# sx3_io_tach.net
KiCad netlist of a schematic drawn in EAGLE
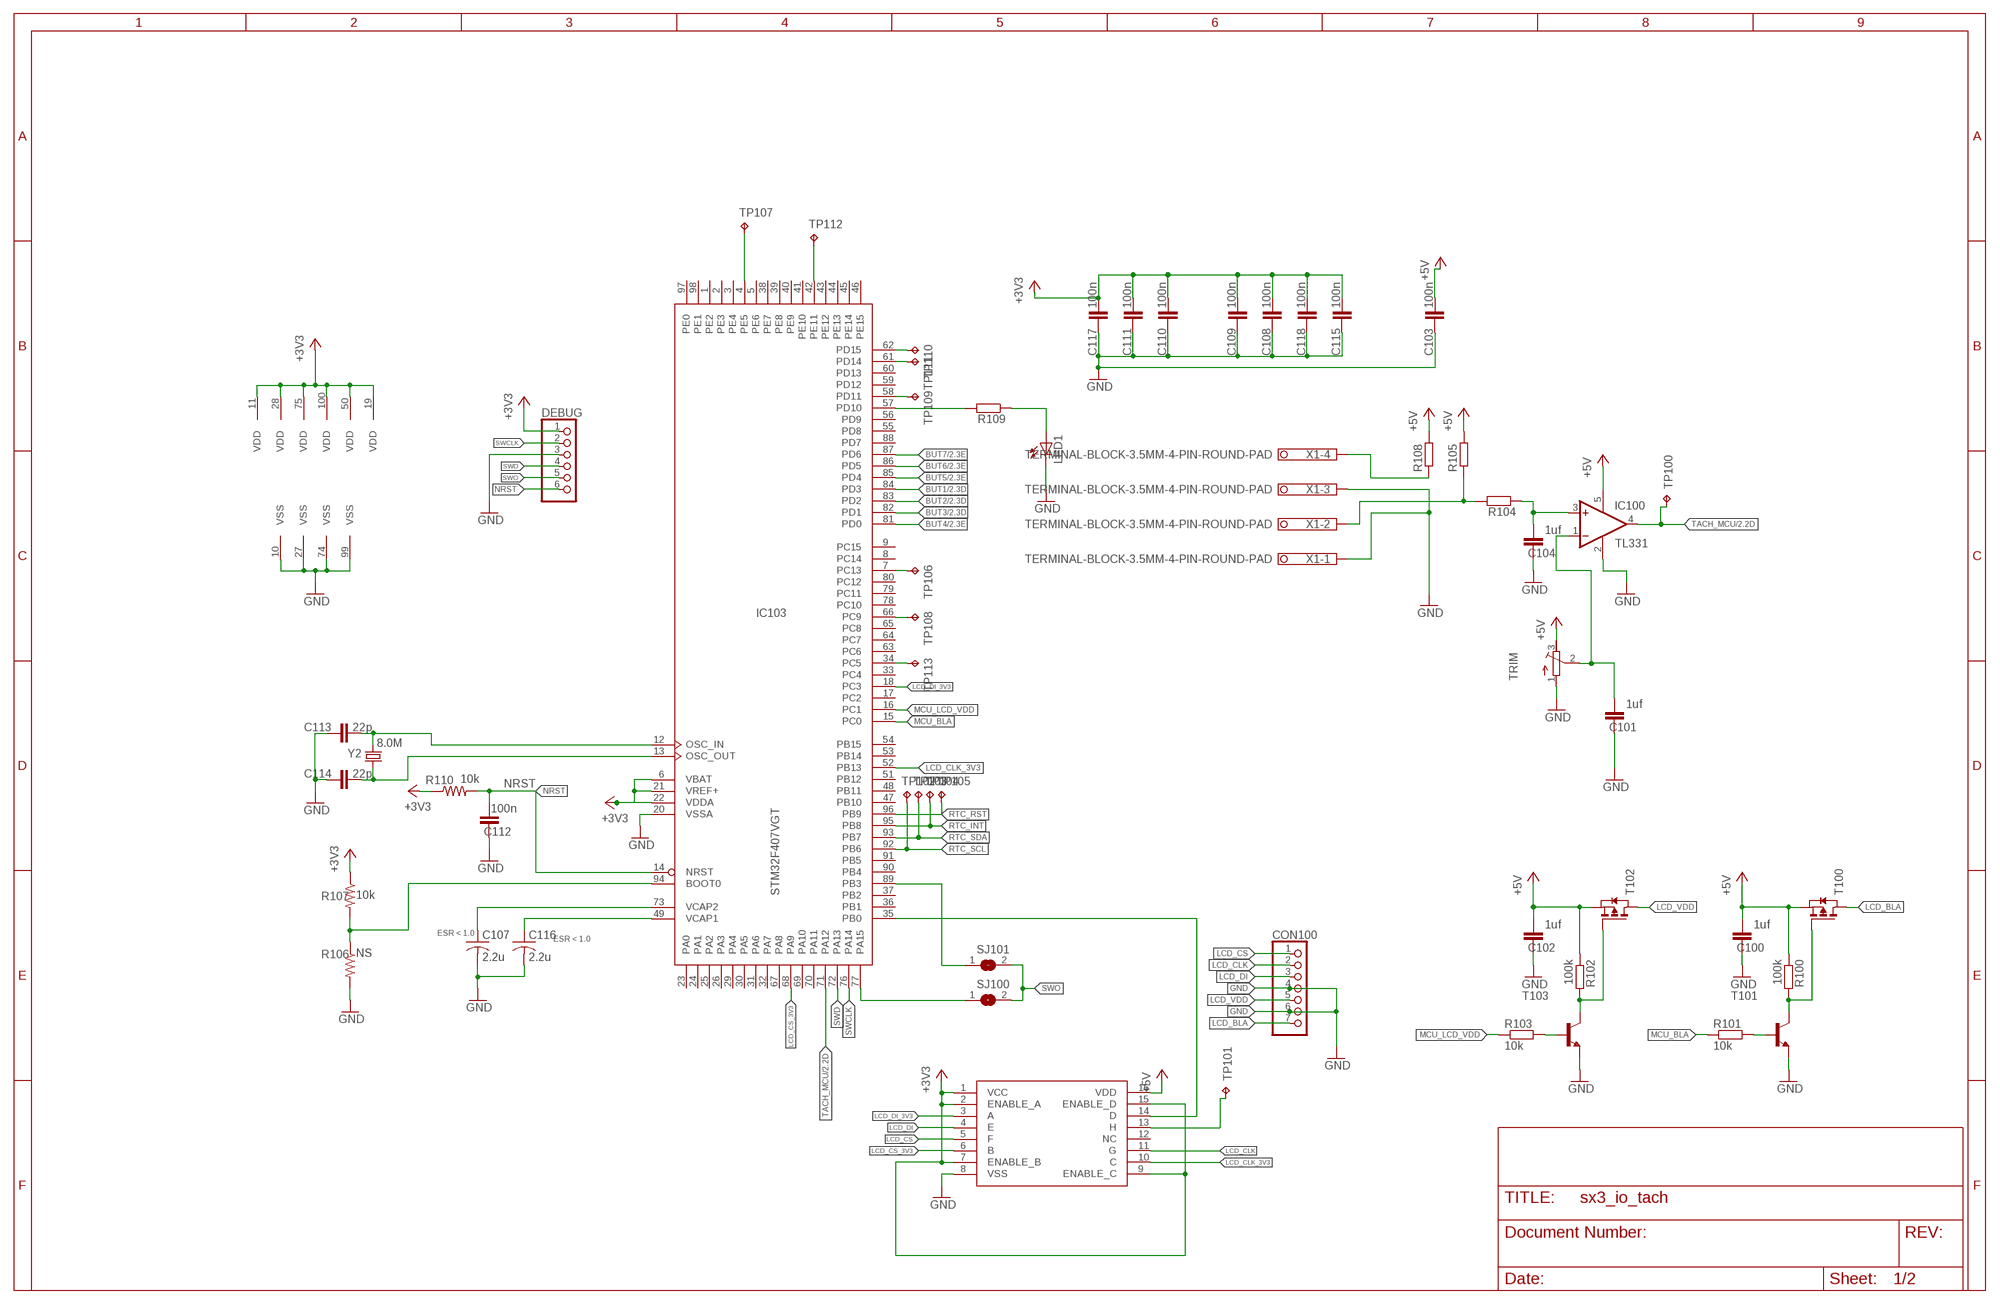
[diagram p0: schematic, sheet 1]
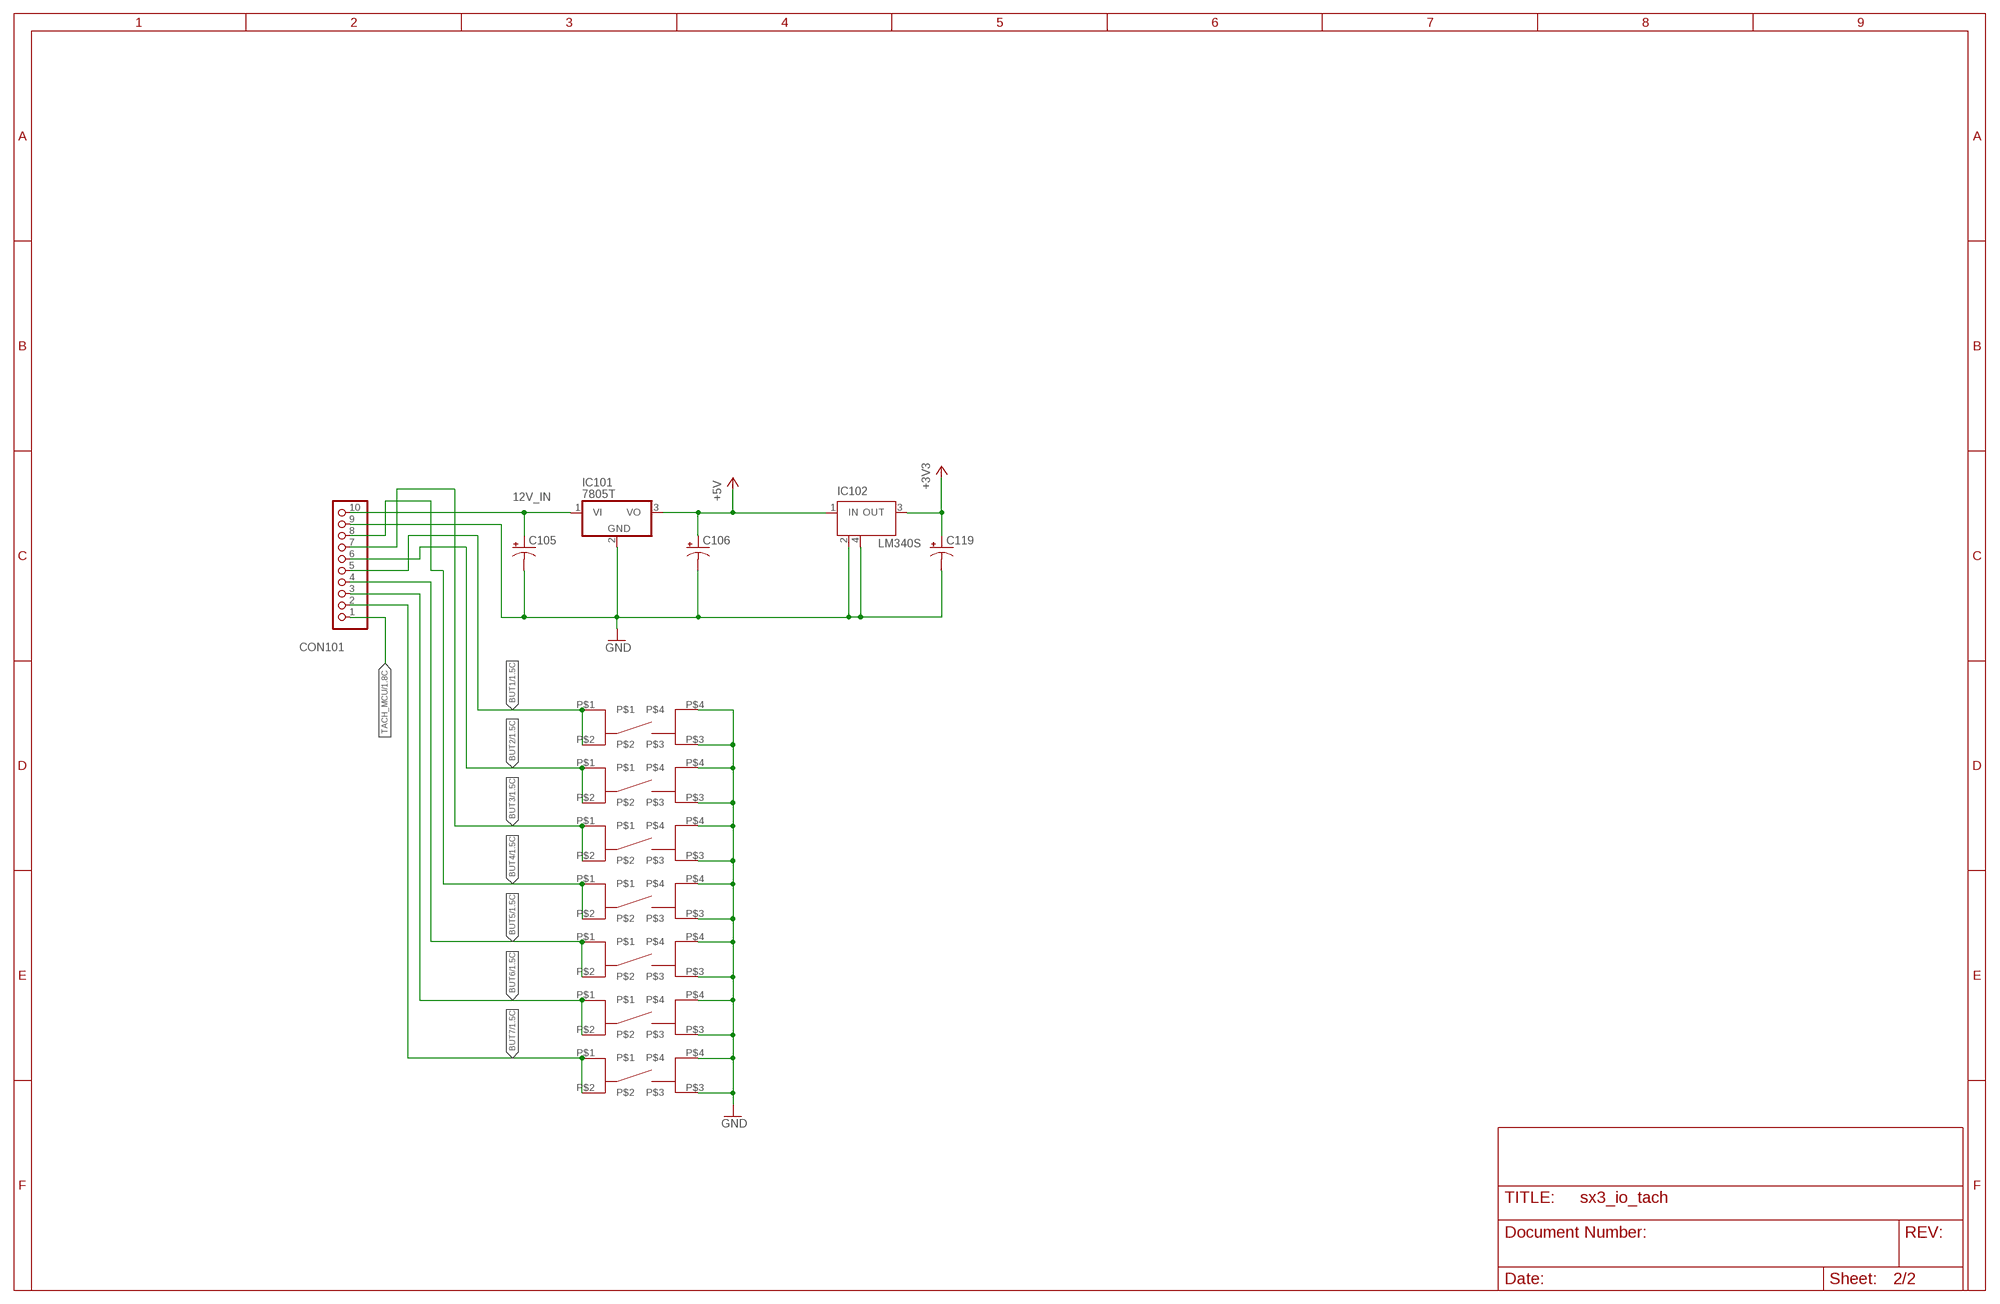
[diagram p1: schematic, sheet 2]

(export (version "E")
  (design (tool "Eeschema 10.0.6"))
  (components
    (comp (ref "C105")
      (value "CPOL-USE2,5-6E")
      (footprint "eagle-import:E2,5-6E")
      (libsource (lib "eagle-import") (part "CPOL-USE2,5-6E"))
    )
    (comp (ref "C106")
      (value "CPOL-USE2,5-6E")
      (footprint "eagle-import:E2,5-6E")
      (libsource (lib "eagle-import") (part "CPOL-USE2,5-6E"))
    )
    (comp (ref "C119")
      (value "CPOL-USE2,5-6E")
      (footprint "eagle-import:E2,5-6E")
      (libsource (lib "eagle-import") (part "CPOL-USE2,5-6E"))
    )
    (comp (ref "CON101")
      (value "PINHD-1X10")
      (footprint "eagle-import:1X10")
      (libsource (lib "eagle-import") (part "PINHD-1X10"))
    )
    (comp (ref "IC101")
      (value "7805T")
      (footprint "eagle-import:TO220H")
      (libsource (lib "eagle-import") (part "78T05"))
    )
    (comp (ref "IC102")
      (value "LM340S")
      (footprint "eagle-import:SOT223")
      (libsource (lib "eagle-import") (part "LM340S"))
    )
    (comp (ref "U$1")
      (value "TE_2-1825910")
      (footprint "eagle-import:TE_2-1825910-7")
      (libsource (lib "eagle-import") (part "TE_2-1825910"))
    )
    (comp (ref "U$2")
      (value "TE_2-1825910")
      (footprint "eagle-import:TE_2-1825910-7")
      (libsource (lib "eagle-import") (part "TE_2-1825910"))
    )
    (comp (ref "U$3")
      (value "TE_2-1825910")
      (footprint "eagle-import:TE_2-1825910-7")
      (libsource (lib "eagle-import") (part "TE_2-1825910"))
    )
    (comp (ref "U$4")
      (value "TE_2-1825910")
      (footprint "eagle-import:TE_2-1825910-7")
      (libsource (lib "eagle-import") (part "TE_2-1825910"))
    )
    (comp (ref "U$5")
      (value "TE_2-1825910")
      (footprint "eagle-import:TE_2-1825910-7")
      (libsource (lib "eagle-import") (part "TE_2-1825910"))
    )
    (comp (ref "U$6")
      (value "TE_2-1825910")
      (footprint "eagle-import:TE_2-1825910-7")
      (libsource (lib "eagle-import") (part "TE_2-1825910"))
    )
    (comp (ref "U$7")
      (value "TE_2-1825910")
      (footprint "eagle-import:TE_2-1825910-7")
      (libsource (lib "eagle-import") (part "TE_2-1825910"))
    )
    (comp (ref "C100")
      (value "1uf")
      (footprint "eagle-import:C0603K")
      (libsource (lib "eagle-import") (part "C-EUC0603K"))
    )
    (comp (ref "C101")
      (value "1uf")
      (footprint "eagle-import:C0603K")
      (libsource (lib "eagle-import") (part "C-EUC0603K"))
    )
    (comp (ref "C102")
      (value "1uf")
      (footprint "eagle-import:C0603K")
      (libsource (lib "eagle-import") (part "C-EUC0603K"))
    )
    (comp (ref "C103")
      (value "100n")
      (footprint "eagle-import:C0603K")
      (libsource (lib "eagle-import") (part "C-EUC0603K"))
    )
    (comp (ref "C104")
      (value "1uf")
      (footprint "eagle-import:C0603K")
      (libsource (lib "eagle-import") (part "C-EUC0603K"))
    )
    (comp (ref "C107")
      (value "2.2u")
      (footprint "eagle-import:C1206")
      (libsource (lib "eagle-import") (part "C-USC1206"))
    )
    (comp (ref "C108")
      (value "100n")
      (footprint "eagle-import:C0603K")
      (libsource (lib "eagle-import") (part "C-EUC0603K"))
    )
    (comp (ref "C109")
      (value "100n")
      (footprint "eagle-import:C0603K")
      (libsource (lib "eagle-import") (part "C-EUC0603K"))
    )
    (comp (ref "C110")
      (value "100n")
      (footprint "eagle-import:C0603K")
      (libsource (lib "eagle-import") (part "C-EUC0603K"))
    )
    (comp (ref "C111")
      (value "100n")
      (footprint "eagle-import:C0603K")
      (libsource (lib "eagle-import") (part "C-EUC0603K"))
    )
    (comp (ref "C112")
      (value "100n")
      (footprint "eagle-import:C0603K")
      (libsource (lib "eagle-import") (part "C-EUC0603K"))
    )
    (comp (ref "C113")
      (value "22p")
      (footprint "eagle-import:C0603K")
      (libsource (lib "eagle-import") (part "C-EUC0603K"))
    )
    (comp (ref "C114")
      (value "22p")
      (footprint "eagle-import:C0603K")
      (libsource (lib "eagle-import") (part "C-EUC0603K"))
    )
    (comp (ref "C115")
      (value "100n")
      (footprint "eagle-import:C0603K")
      (libsource (lib "eagle-import") (part "C-EUC0603K"))
    )
    (comp (ref "C116")
      (value "2.2u")
      (footprint "eagle-import:C1206")
      (libsource (lib "eagle-import") (part "C-USC1206"))
    )
    (comp (ref "C117")
      (value "100n")
      (footprint "eagle-import:C0603K")
      (libsource (lib "eagle-import") (part "C-EUC0603K"))
    )
    (comp (ref "C118")
      (value "100n")
      (footprint "eagle-import:C0603K")
      (libsource (lib "eagle-import") (part "C-EUC0603K"))
    )
    (comp (ref "CON100")
      (value "PINHD-1X7")
      (footprint "eagle-import:1X07")
      (libsource (lib "eagle-import") (part "PINHD-1X7"))
    )
    (comp (ref "DEBUG")
      (value "PINHD-1X6")
      (footprint "eagle-import:1X06")
      (libsource (lib "eagle-import") (part "PINHD-1X6"))
    )
    (comp (ref "IC100")
      (value "TL331")
      (footprint "eagle-import:DBV-R-PDSO-G5")
      (libsource (lib "eagle-import") (part "TL331"))
    )
    (comp (ref "IC103")
      (value "STM32F407VGT")
      (footprint "eagle-import:LQFP100")
      (libsource (lib "eagle-import") (part "STM32F407VTG"))
    )
    (comp (ref "LED1")
      (value "LED_ELD260")
      (footprint "eagle-import:LED_LD260")
      (libsource (lib "eagle-import") (part "LED_ELD260"))
    )
    (comp (ref "R100")
      (value "100k")
      (footprint "eagle-import:R0603")
      (libsource (lib "eagle-import") (part "R-EU_R0603"))
    )
    (comp (ref "R101")
      (value "10k")
      (footprint "eagle-import:R0603")
      (libsource (lib "eagle-import") (part "R-EU_R0603"))
    )
    (comp (ref "R102")
      (value "100k")
      (footprint "eagle-import:R0603")
      (libsource (lib "eagle-import") (part "R-EU_R0603"))
    )
    (comp (ref "R103")
      (value "10k")
      (footprint "eagle-import:R0603")
      (libsource (lib "eagle-import") (part "R-EU_R0603"))
    )
    (comp (ref "R104")
      (value "R-EU_R0603")
      (footprint "eagle-import:R0603")
      (libsource (lib "eagle-import") (part "R-EU_R0603"))
    )
    (comp (ref "R105")
      (value "R-EU_R0603")
      (footprint "eagle-import:R0603")
      (libsource (lib "eagle-import") (part "R-EU_R0603"))
    )
    (comp (ref "R106")
      (value "NS")
      (footprint "eagle-import:R0603")
      (libsource (lib "eagle-import") (part "R-US_R0603"))
    )
    (comp (ref "R107")
      (value "10k")
      (footprint "eagle-import:R0603")
      (libsource (lib "eagle-import") (part "R-US_R0603"))
    )
    (comp (ref "R108")
      (value "R-EU_R0603")
      (footprint "eagle-import:R0603")
      (libsource (lib "eagle-import") (part "R-EU_R0603"))
    )
    (comp (ref "R109")
      (value "R-EU_R0603")
      (footprint "eagle-import:R0603")
      (libsource (lib "eagle-import") (part "R-EU_R0603"))
    )
    (comp (ref "R110")
      (value "10k")
      (footprint "eagle-import:R0603")
      (libsource (lib "eagle-import") (part "R-US_R0603"))
    )
    (comp (ref "SJ100")
      (value "SJ")
      (footprint "eagle-import:SJ")
      (libsource (lib "eagle-import") (part "SJ"))
    )
    (comp (ref "SJ101")
      (value "SJ")
      (footprint "eagle-import:SJ")
      (libsource (lib "eagle-import") (part "SJ"))
    )
    (comp (ref "T100")
      (value "PMOSSOT23")
      (footprint "eagle-import:SOT-23")
      (libsource (lib "eagle-import") (part "PMOSSOT23"))
    )
    (comp (ref "T101")
      (value "BC817-NPN-SOT23-BEC")
      (footprint "eagle-import:SOT23-BEC")
      (libsource (lib "eagle-import") (part "-NPN-SOT23-BECBC817"))
    )
    (comp (ref "T102")
      (value "PMOSSOT23")
      (footprint "eagle-import:SOT-23")
      (libsource (lib "eagle-import") (part "PMOSSOT23"))
    )
    (comp (ref "T103")
      (value "BC817-NPN-SOT23-BEC")
      (footprint "eagle-import:SOT23-BEC")
      (libsource (lib "eagle-import") (part "-NPN-SOT23-BECBC817"))
    )
    (comp (ref "TP100")
      (value "TPB1,27")
      (footprint "eagle-import:B1,27")
      (libsource (lib "eagle-import") (part "TPB1,27"))
    )
    (comp (ref "TP101")
      (value "TPB1,27")
      (footprint "eagle-import:B1,27")
      (libsource (lib "eagle-import") (part "TPB1,27"))
    )
    (comp (ref "TP102")
      (value "TPTP17R")
      (footprint "eagle-import:TP17R")
      (libsource (lib "eagle-import") (part "TPTP17R"))
    )
    (comp (ref "TP103")
      (value "TPTP17R")
      (footprint "eagle-import:TP17R")
      (libsource (lib "eagle-import") (part "TPTP17R"))
    )
    (comp (ref "TP104")
      (value "TPTP17R")
      (footprint "eagle-import:TP17R")
      (libsource (lib "eagle-import") (part "TPTP17R"))
    )
    (comp (ref "TP105")
      (value "TPTP17R")
      (footprint "eagle-import:TP17R")
      (libsource (lib "eagle-import") (part "TPTP17R"))
    )
    (comp (ref "TP106")
      (value "TPTP17R")
      (footprint "eagle-import:TP17R")
      (libsource (lib "eagle-import") (part "TPTP17R"))
    )
    (comp (ref "TP107")
      (value "TPTP17R")
      (footprint "eagle-import:TP17R")
      (libsource (lib "eagle-import") (part "TPTP17R"))
    )
    (comp (ref "TP108")
      (value "TPTP17R")
      (footprint "eagle-import:TP17R")
      (libsource (lib "eagle-import") (part "TPTP17R"))
    )
    (comp (ref "TP109")
      (value "TPTP17R")
      (footprint "eagle-import:TP17R")
      (libsource (lib "eagle-import") (part "TPTP17R"))
    )
    (comp (ref "TP110")
      (value "TPTP17R")
      (footprint "eagle-import:TP17R")
      (libsource (lib "eagle-import") (part "TPTP17R"))
    )
    (comp (ref "TP111")
      (value "TPTP17R")
      (footprint "eagle-import:TP17R")
      (libsource (lib "eagle-import") (part "TPTP17R"))
    )
    (comp (ref "TP112")
      (value "TPTP17R")
      (footprint "eagle-import:TP17R")
      (libsource (lib "eagle-import") (part "TPTP17R"))
    )
    (comp (ref "TP113")
      (value "TPTP17R")
      (footprint "eagle-import:TP17R")
      (libsource (lib "eagle-import") (part "TPTP17R"))
    )
    (comp (ref "TRIM")
      (value "R-TRIMM3296W")
      (footprint "eagle-import:RTRIM3296W")
      (libsource (lib "eagle-import") (part "R-TRIMM3296W"))
    )
    (comp (ref "U$100")
      (value "CD40109BPWR")
      (footprint "eagle-import:TSSOP16")
      (libsource (lib "eagle-import") (part "CD40109BPWR"))
    )
    (comp (ref "X1")
      (value "TERMINAL-BLOCK-3.5MM-4-PIN-ROUND-PAD")
      (footprint "eagle-import:TERMINAL-BLOCK-4-PIN-3.5MM-ROUND-PAD")
      (libsource (lib "eagle-import") (part "TERMINAL-BLOCK-3.5MM-4-PIN-ROUND-PAD"))
    )
    (comp (ref "Y2")
      (value "8.0M")
      (footprint "eagle-import:HC49U-V")
      (libsource (lib "eagle-import") (part "CRYSTALHC49UV"))
    )
  )
  (nets
    (net (code "1") (name "+3V3") (class "Default")
      (node (ref "C108") (pin "2") (pinfunction "2_2") (pintype "passive"))
      (node (ref "C109") (pin "2") (pinfunction "2_2") (pintype "passive"))
      (node (ref "C110") (pin "2") (pinfunction "2_2") (pintype "passive"))
      (node (ref "C111") (pin "2") (pinfunction "2_2") (pintype "passive"))
      (node (ref "C115") (pin "2") (pinfunction "2_2") (pintype "passive"))
      (node (ref "C117") (pin "2") (pinfunction "2_2") (pintype "passive"))
      (node (ref "C118") (pin "2") (pinfunction "2_2") (pintype "passive"))
      (node (ref "C119") (pin "+") (pinfunction "+_+") (pintype "passive"))
      (node (ref "DEBUG") (pin "1") (pinfunction "1_1") (pintype "passive"))
      (node (ref "IC102") (pin "3") (pinfunction "OUT_3") (pintype "passive"))
      (node (ref "IC103") (pin "100") (pinfunction "VDD_100") (pintype "power_in"))
      (node (ref "IC103") (pin "11") (pinfunction "VDD_11") (pintype "power_in"))
      (node (ref "IC103") (pin "19") (pinfunction "VDD_19") (pintype "power_in"))
      (node (ref "IC103") (pin "21") (pinfunction "VREF+_21") (pintype "power_in"))
      (node (ref "IC103") (pin "22") (pinfunction "VDDA_22") (pintype "power_in"))
      (node (ref "IC103") (pin "28") (pinfunction "VDD_28") (pintype "power_in"))
      (node (ref "IC103") (pin "50") (pinfunction "VDD_50") (pintype "power_in"))
      (node (ref "IC103") (pin "6") (pinfunction "VBAT_6") (pintype "power_in"))
      (node (ref "IC103") (pin "75") (pinfunction "VDD_75") (pintype "power_in"))
      (node (ref "R107") (pin "1") (pinfunction "1_1") (pintype "passive"))
      (node (ref "R110") (pin "1") (pinfunction "1_1") (pintype "passive"))
      (node (ref "U$100") (pin "1") (pinfunction "VCC_1") (pintype "bidirectional"))
      (node (ref "U$100") (pin "15") (pinfunction "ENABLE_D_15") (pintype "bidirectional"))
      (node (ref "U$100") (pin "2") (pinfunction "ENABLE_A_2") (pintype "bidirectional"))
      (node (ref "U$100") (pin "7") (pinfunction "ENABLE_B_7") (pintype "bidirectional"))
      (node (ref "U$100") (pin "9") (pinfunction "ENABLE_C_9") (pintype "bidirectional"))
    )
    (net (code "2") (name "+5V") (class "Default")
      (node (ref "C100") (pin "2") (pinfunction "2_2") (pintype "passive"))
      (node (ref "C102") (pin "2") (pinfunction "2_2") (pintype "passive"))
      (node (ref "C103") (pin "2") (pinfunction "2_2") (pintype "passive"))
      (node (ref "C106") (pin "+") (pinfunction "+_+") (pintype "passive"))
      (node (ref "IC100") (pin "5") (pinfunction "V+_5") (pintype "power_in"))
      (node (ref "IC101") (pin "3") (pinfunction "VO_3") (pintype "passive"))
      (node (ref "IC102") (pin "1") (pinfunction "IN_1") (pintype "input"))
      (node (ref "R100") (pin "1") (pinfunction "1_1") (pintype "passive"))
      (node (ref "R102") (pin "1") (pinfunction "1_1") (pintype "passive"))
      (node (ref "R105") (pin "2") (pinfunction "2_2") (pintype "passive"))
      (node (ref "R108") (pin "2") (pinfunction "2_2") (pintype "passive"))
      (node (ref "T100") (pin "2") (pinfunction "S_2") (pintype "passive"))
      (node (ref "T102") (pin "2") (pinfunction "S_2") (pintype "passive"))
      (node (ref "TRIM") (pin "3") (pinfunction "E_3") (pintype "passive"))
      (node (ref "U$100") (pin "16") (pinfunction "VDD_16") (pintype "bidirectional"))
    )
    (net (code "3") (name "12V_IN") (class "Default")
      (node (ref "C105") (pin "+") (pinfunction "+_+") (pintype "passive"))
      (node (ref "CON101") (pin "10") (pinfunction "10_10") (pintype "passive"))
      (node (ref "IC101") (pin "1") (pinfunction "VI_1") (pintype "input"))
    )
    (net (code "4") (name "BUT1") (class "Default")
      (node (ref "CON101") (pin "5") (pinfunction "5_5") (pintype "passive"))
      (node (ref "IC103") (pin "84") (pinfunction "PD3_84") (pintype "bidirectional"))
      (node (ref "U$7") (pin "P$1") (pinfunction "P$1_P$1") (pintype "bidirectional"))
      (node (ref "U$7") (pin "P$2") (pinfunction "P$2_P$2") (pintype "bidirectional"))
    )
    (net (code "5") (name "BUT2") (class "Default")
      (node (ref "CON101") (pin "6") (pinfunction "6_6") (pintype "passive"))
      (node (ref "IC103") (pin "83") (pinfunction "PD2_83") (pintype "bidirectional"))
      (node (ref "U$5") (pin "P$1") (pinfunction "P$1_P$1") (pintype "bidirectional"))
      (node (ref "U$5") (pin "P$2") (pinfunction "P$2_P$2") (pintype "bidirectional"))
    )
    (net (code "6") (name "BUT3") (class "Default")
      (node (ref "CON101") (pin "7") (pinfunction "7_7") (pintype "passive"))
      (node (ref "IC103") (pin "82") (pinfunction "PD1_82") (pintype "bidirectional"))
      (node (ref "U$3") (pin "P$1") (pinfunction "P$1_P$1") (pintype "bidirectional"))
      (node (ref "U$3") (pin "P$2") (pinfunction "P$2_P$2") (pintype "bidirectional"))
    )
    (net (code "7") (name "BUT4") (class "Default")
      (node (ref "CON101") (pin "8") (pinfunction "8_8") (pintype "passive"))
      (node (ref "IC103") (pin "81") (pinfunction "PD0_81") (pintype "bidirectional"))
      (node (ref "U$1") (pin "P$1") (pinfunction "P$1_P$1") (pintype "bidirectional"))
      (node (ref "U$1") (pin "P$2") (pinfunction "P$2_P$2") (pintype "bidirectional"))
    )
    (net (code "8") (name "BUT5") (class "Default")
      (node (ref "CON101") (pin "4") (pinfunction "4_4") (pintype "passive"))
      (node (ref "IC103") (pin "85") (pinfunction "PD4_85") (pintype "bidirectional"))
      (node (ref "U$2") (pin "P$1") (pinfunction "P$1_P$1") (pintype "bidirectional"))
      (node (ref "U$2") (pin "P$2") (pinfunction "P$2_P$2") (pintype "bidirectional"))
    )
    (net (code "9") (name "BUT6") (class "Default")
      (node (ref "CON101") (pin "3") (pinfunction "3_3") (pintype "passive"))
      (node (ref "IC103") (pin "86") (pinfunction "PD5_86") (pintype "bidirectional"))
      (node (ref "U$4") (pin "P$1") (pinfunction "P$1_P$1") (pintype "bidirectional"))
      (node (ref "U$4") (pin "P$2") (pinfunction "P$2_P$2") (pintype "bidirectional"))
    )
    (net (code "10") (name "BUT7") (class "Default")
      (node (ref "CON101") (pin "2") (pinfunction "2_2") (pintype "passive"))
      (node (ref "IC103") (pin "87") (pinfunction "PD6_87") (pintype "bidirectional"))
      (node (ref "U$6") (pin "P$1") (pinfunction "P$1_P$1") (pintype "bidirectional"))
      (node (ref "U$6") (pin "P$2") (pinfunction "P$2_P$2") (pintype "bidirectional"))
    )
    (net (code "11") (name "GND") (class "Default")
      (node (ref "C100") (pin "1") (pinfunction "1_1") (pintype "passive"))
      (node (ref "C101") (pin "1") (pinfunction "1_1") (pintype "passive"))
      (node (ref "C102") (pin "1") (pinfunction "1_1") (pintype "passive"))
      (node (ref "C103") (pin "1") (pinfunction "1_1") (pintype "passive"))
      (node (ref "C104") (pin "1") (pinfunction "1_1") (pintype "passive"))
      (node (ref "C105") (pin "-") (pinfunction "-_-") (pintype "passive"))
      (node (ref "C106") (pin "-") (pinfunction "-_-") (pintype "passive"))
      (node (ref "C107") (pin "2") (pinfunction "2_2") (pintype "passive"))
      (node (ref "C108") (pin "1") (pinfunction "1_1") (pintype "passive"))
      (node (ref "C109") (pin "1") (pinfunction "1_1") (pintype "passive"))
      (node (ref "C110") (pin "1") (pinfunction "1_1") (pintype "passive"))
      (node (ref "C111") (pin "1") (pinfunction "1_1") (pintype "passive"))
      (node (ref "C112") (pin "1") (pinfunction "1_1") (pintype "passive"))
      (node (ref "C113") (pin "1") (pinfunction "1_1") (pintype "passive"))
      (node (ref "C114") (pin "1") (pinfunction "1_1") (pintype "passive"))
      (node (ref "C115") (pin "1") (pinfunction "1_1") (pintype "passive"))
      (node (ref "C116") (pin "2") (pinfunction "2_2") (pintype "passive"))
      (node (ref "C117") (pin "1") (pinfunction "1_1") (pintype "passive"))
      (node (ref "C118") (pin "1") (pinfunction "1_1") (pintype "passive"))
      (node (ref "C119") (pin "-") (pinfunction "-_-") (pintype "passive"))
      (node (ref "CON100") (pin "4") (pinfunction "4_4") (pintype "passive"))
      (node (ref "CON100") (pin "6") (pinfunction "6_6") (pintype "passive"))
      (node (ref "CON101") (pin "9") (pinfunction "9_9") (pintype "passive"))
      (node (ref "DEBUG") (pin "3") (pinfunction "3_3") (pintype "passive"))
      (node (ref "IC100") (pin "2") (pinfunction "GND_2") (pintype "power_in"))
      (node (ref "IC101") (pin "2") (pinfunction "GND_2") (pintype "passive"))
      (node (ref "IC102") (pin "2") (pinfunction "GND_2") (pintype "power_in"))
      (node (ref "IC102") (pin "4") (pinfunction "GND_4") (pintype "power_in"))
      (node (ref "IC103") (pin "10") (pinfunction "VSS_10") (pintype "power_in"))
      (node (ref "IC103") (pin "20") (pinfunction "VSSA_20") (pintype "power_in"))
      (node (ref "IC103") (pin "27") (pinfunction "VSS_27") (pintype "power_in"))
      (node (ref "IC103") (pin "74") (pinfunction "VSS_74") (pintype "power_in"))
      (node (ref "IC103") (pin "99") (pinfunction "VSS_99") (pintype "power_in"))
      (node (ref "LED1") (pin "K") (pinfunction "C_K") (pintype "passive"))
      (node (ref "R106") (pin "2") (pinfunction "2_2") (pintype "passive"))
      (node (ref "T101") (pin "E") (pinfunction "E_E") (pintype "passive"))
      (node (ref "T103") (pin "E") (pinfunction "E_E") (pintype "passive"))
      (node (ref "TRIM") (pin "1") (pinfunction "A_1") (pintype "passive"))
      (node (ref "U$1") (pin "P$3") (pinfunction "P$3_P$3") (pintype "bidirectional"))
      (node (ref "U$1") (pin "P$4") (pinfunction "P$4_P$4") (pintype "bidirectional"))
      (node (ref "U$100") (pin "8") (pinfunction "VSS_8") (pintype "bidirectional"))
      (node (ref "U$2") (pin "P$3") (pinfunction "P$3_P$3") (pintype "bidirectional"))
      (node (ref "U$2") (pin "P$4") (pinfunction "P$4_P$4") (pintype "bidirectional"))
      (node (ref "U$3") (pin "P$3") (pinfunction "P$3_P$3") (pintype "bidirectional"))
      (node (ref "U$3") (pin "P$4") (pinfunction "P$4_P$4") (pintype "bidirectional"))
      (node (ref "U$4") (pin "P$3") (pinfunction "P$3_P$3") (pintype "bidirectional"))
      (node (ref "U$4") (pin "P$4") (pinfunction "P$4_P$4") (pintype "bidirectional"))
      (node (ref "U$5") (pin "P$3") (pinfunction "P$3_P$3") (pintype "bidirectional"))
      (node (ref "U$5") (pin "P$4") (pinfunction "P$4_P$4") (pintype "bidirectional"))
      (node (ref "U$6") (pin "P$3") (pinfunction "P$3_P$3") (pintype "bidirectional"))
      (node (ref "U$6") (pin "P$4") (pinfunction "P$4_P$4") (pintype "bidirectional"))
      (node (ref "U$7") (pin "P$3") (pinfunction "P$3_P$3") (pintype "bidirectional"))
      (node (ref "U$7") (pin "P$4") (pinfunction "P$4_P$4") (pintype "bidirectional"))
      (node (ref "X1") (pin "1") (pinfunction "K_1") (pintype "passive"))
      (node (ref "X1") (pin "3") (pinfunction "K_3") (pintype "passive"))
    )
    (net (code "12") (name "LCD_BLA") (class "Default")
      (node (ref "CON100") (pin "7") (pinfunction "7_7") (pintype "passive"))
      (node (ref "T100") (pin "1") (pinfunction "D_1") (pintype "passive"))
    )
    (net (code "13") (name "LCD_CLK") (class "Default")
      (node (ref "CON100") (pin "2") (pinfunction "2_2") (pintype "passive"))
      (node (ref "U$100") (pin "11") (pinfunction "G_11") (pintype "bidirectional"))
    )
    (net (code "14") (name "LCD_CLK_3V3") (class "Default")
      (node (ref "IC103") (pin "52") (pinfunction "PB13_52") (pintype "bidirectional"))
      (node (ref "U$100") (pin "10") (pinfunction "C_10") (pintype "bidirectional"))
    )
    (net (code "15") (name "LCD_CS") (class "Default")
      (node (ref "CON100") (pin "1") (pinfunction "1_1") (pintype "passive"))
      (node (ref "U$100") (pin "5") (pinfunction "F_5") (pintype "bidirectional"))
    )
    (net (code "16") (name "LCD_CS_3V3") (class "Default")
      (node (ref "IC103") (pin "68") (pinfunction "PA9_68") (pintype "bidirectional"))
      (node (ref "U$100") (pin "6") (pinfunction "B_6") (pintype "bidirectional"))
    )
    (net (code "17") (name "LCD_DI") (class "Default")
      (node (ref "CON100") (pin "3") (pinfunction "3_3") (pintype "passive"))
      (node (ref "U$100") (pin "4") (pinfunction "E_4") (pintype "bidirectional"))
    )
    (net (code "18") (name "LCD_DI_3V3") (class "Default")
      (node (ref "IC103") (pin "18") (pinfunction "PC3_18") (pintype "bidirectional"))
      (node (ref "U$100") (pin "3") (pinfunction "A_3") (pintype "bidirectional"))
    )
    (net (code "19") (name "LCD_VDD") (class "Default")
      (node (ref "CON100") (pin "5") (pinfunction "5_5") (pintype "passive"))
      (node (ref "T102") (pin "1") (pinfunction "D_1") (pintype "passive"))
    )
    (net (code "20") (name "MCU_BLA") (class "Default")
      (node (ref "IC103") (pin "15") (pinfunction "PC0_15") (pintype "bidirectional"))
      (node (ref "R101") (pin "1") (pinfunction "1_1") (pintype "passive"))
    )
    (net (code "21") (name "MCU_LCD_VDD") (class "Default")
      (node (ref "IC103") (pin "16") (pinfunction "PC1_16") (pintype "bidirectional"))
      (node (ref "R103") (pin "1") (pinfunction "1_1") (pintype "passive"))
    )
    (net (code "22") (name "NRST") (class "Default")
      (node (ref "C112") (pin "2") (pinfunction "2_2") (pintype "passive"))
      (node (ref "DEBUG") (pin "6") (pinfunction "6_6") (pintype "passive"))
      (node (ref "IC103") (pin "14") (pinfunction "NRST_14") (pintype "bidirectional"))
      (node (ref "R110") (pin "2") (pinfunction "2_2") (pintype "passive"))
    )
    (net (code "23") (name "Net-(IC100-+IN)") (class "Default")
      (node (ref "C104") (pin "2") (pinfunction "2_2") (pintype "passive"))
      (node (ref "IC100") (pin "3") (pinfunction "+IN_3") (pintype "input"))
      (node (ref "R104") (pin "1") (pinfunction "1_1") (pintype "passive"))
    )
    (net (code "24") (name "Net-(IC100--IN)") (class "Default")
      (node (ref "C101") (pin "2") (pinfunction "2_2") (pintype "passive"))
      (node (ref "IC100") (pin "1") (pinfunction "-IN_1") (pintype "input"))
      (node (ref "TRIM") (pin "2") (pinfunction "S_2") (pintype "passive"))
    )
    (net (code "25") (name "Net-(IC103A-BOOT0)") (class "Default")
      (node (ref "IC103") (pin "94") (pinfunction "BOOT0_94") (pintype "input"))
      (node (ref "R106") (pin "1") (pinfunction "1_1") (pintype "passive"))
      (node (ref "R107") (pin "2") (pinfunction "2_2") (pintype "passive"))
    )
    (net (code "26") (name "Net-(IC103A-OSC_IN)") (class "Default")
      (node (ref "C113") (pin "2") (pinfunction "2_2") (pintype "passive"))
      (node (ref "IC103") (pin "12") (pinfunction "OSC_IN_12") (pintype "bidirectional"))
      (node (ref "Y2") (pin "2") (pinfunction "2_2") (pintype "passive"))
    )
    (net (code "27") (name "Net-(IC103A-OSC_OUT)") (class "Default")
      (node (ref "C114") (pin "2") (pinfunction "2_2") (pintype "passive"))
      (node (ref "IC103") (pin "13") (pinfunction "OSC_OUT_13") (pintype "bidirectional"))
      (node (ref "Y2") (pin "1") (pinfunction "1_1") (pintype "passive"))
    )
    (net (code "28") (name "Net-(IC103A-PA15)") (class "Default")
      (node (ref "IC103") (pin "77") (pinfunction "PA15_77") (pintype "bidirectional"))
      (node (ref "SJ100") (pin "1") (pinfunction "1_1") (pintype "passive"))
    )
    (net (code "29") (name "Net-(IC103A-PB0)") (class "Default")
      (node (ref "IC103") (pin "35") (pinfunction "PB0_35") (pintype "bidirectional"))
      (node (ref "U$100") (pin "14") (pinfunction "D_14") (pintype "bidirectional"))
    )
    (net (code "30") (name "Net-(IC103A-PB3)") (class "Default")
      (node (ref "IC103") (pin "89") (pinfunction "PB3_89") (pintype "bidirectional"))
      (node (ref "SJ101") (pin "1") (pinfunction "1_1") (pintype "passive"))
    )
    (net (code "31") (name "Net-(IC103A-PC5)") (class "Default")
      (node (ref "IC103") (pin "34") (pinfunction "PC5_34") (pintype "bidirectional"))
      (node (ref "TP113") (pin "TP") (pinfunction "TP_TP") (pintype "input"))
    )
    (net (code "32") (name "Net-(IC103A-PC9)") (class "Default")
      (node (ref "IC103") (pin "66") (pinfunction "PC9_66") (pintype "bidirectional"))
      (node (ref "TP108") (pin "TP") (pinfunction "TP_TP") (pintype "input"))
    )
    (net (code "33") (name "Net-(IC103A-PC13)") (class "Default")
      (node (ref "IC103") (pin "7") (pinfunction "PC13_7") (pintype "bidirectional"))
      (node (ref "TP106") (pin "TP") (pinfunction "TP_TP") (pintype "input"))
    )
    (net (code "34") (name "Net-(IC103A-PD10)") (class "Default")
      (node (ref "IC103") (pin "57") (pinfunction "PD10_57") (pintype "bidirectional"))
      (node (ref "R109") (pin "2") (pinfunction "2_2") (pintype "passive"))
    )
    (net (code "35") (name "Net-(IC103A-PD11)") (class "Default")
      (node (ref "IC103") (pin "58") (pinfunction "PD11_58") (pintype "bidirectional"))
      (node (ref "TP109") (pin "TP") (pinfunction "TP_TP") (pintype "input"))
    )
    (net (code "36") (name "Net-(IC103A-PD14)") (class "Default")
      (node (ref "IC103") (pin "61") (pinfunction "PD14_61") (pintype "bidirectional"))
      (node (ref "TP111") (pin "TP") (pinfunction "TP_TP") (pintype "input"))
    )
    (net (code "37") (name "Net-(IC103A-PD15)") (class "Default")
      (node (ref "IC103") (pin "62") (pinfunction "PD15_62") (pintype "bidirectional"))
      (node (ref "TP110") (pin "TP") (pinfunction "TP_TP") (pintype "input"))
    )
    (net (code "38") (name "Net-(IC103A-PE5)") (class "Default")
      (node (ref "IC103") (pin "4") (pinfunction "PE5_4") (pintype "bidirectional"))
      (node (ref "TP107") (pin "TP") (pinfunction "TP_TP") (pintype "input"))
    )
    (net (code "39") (name "Net-(IC103A-PE11)") (class "Default")
      (node (ref "IC103") (pin "42") (pinfunction "PE11_42") (pintype "bidirectional"))
      (node (ref "TP112") (pin "TP") (pinfunction "TP_TP") (pintype "input"))
    )
    (net (code "40") (name "Net-(IC103A-VCAP1)") (class "Default")
      (node (ref "C116") (pin "1") (pinfunction "1_1") (pintype "passive"))
      (node (ref "IC103") (pin "49") (pinfunction "VCAP1_49") (pintype "power_in"))
    )
    (net (code "41") (name "Net-(IC103A-VCAP2)") (class "Default")
      (node (ref "C107") (pin "1") (pinfunction "1_1") (pintype "passive"))
      (node (ref "IC103") (pin "73") (pinfunction "VCAP2_73") (pintype "power_in"))
    )
    (net (code "42") (name "Net-(LED1-PadA)") (class "Default")
      (node (ref "LED1") (pin "A") (pinfunction "A_A") (pintype "passive"))
      (node (ref "R109") (pin "1") (pinfunction "1_1") (pintype "passive"))
    )
    (net (code "43") (name "Net-(R101-Pad2)") (class "Default")
      (node (ref "R101") (pin "2") (pinfunction "2_2") (pintype "passive"))
      (node (ref "T101") (pin "B") (pinfunction "B_B") (pintype "passive"))
    )
    (net (code "44") (name "Net-(R103-Pad2)") (class "Default")
      (node (ref "R103") (pin "2") (pinfunction "2_2") (pintype "passive"))
      (node (ref "T103") (pin "B") (pinfunction "B_B") (pintype "passive"))
    )
    (net (code "45") (name "Net-(T100-G)") (class "Default")
      (node (ref "R100") (pin "2") (pinfunction "2_2") (pintype "passive"))
      (node (ref "T100") (pin "3") (pinfunction "G_3") (pintype "passive"))
      (node (ref "T101") (pin "C") (pinfunction "C_C") (pintype "passive"))
    )
    (net (code "46") (name "Net-(T102-G)") (class "Default")
      (node (ref "R102") (pin "2") (pinfunction "2_2") (pintype "passive"))
      (node (ref "T102") (pin "3") (pinfunction "G_3") (pintype "passive"))
      (node (ref "T103") (pin "C") (pinfunction "C_C") (pintype "passive"))
    )
    (net (code "47") (name "Net-(U$100-H)") (class "Default")
      (node (ref "TP101") (pin "TP") (pinfunction "TP_TP") (pintype "input"))
      (node (ref "U$100") (pin "13") (pinfunction "H_13") (pintype "bidirectional"))
    )
    (net (code "48") (name "Net-(X1B-K)") (class "Default")
      (node (ref "R104") (pin "2") (pinfunction "2_2") (pintype "passive"))
      (node (ref "R105") (pin "1") (pinfunction "1_1") (pintype "passive"))
      (node (ref "X1") (pin "2") (pinfunction "K_2") (pintype "passive"))
    )
    (net (code "49") (name "Net-(X1D-K)") (class "Default")
      (node (ref "R108") (pin "1") (pinfunction "1_1") (pintype "passive"))
      (node (ref "X1") (pin "4") (pinfunction "K_4") (pintype "passive"))
    )
    (net (code "50") (name "RTC_INT") (class "Default")
      (node (ref "IC103") (pin "95") (pinfunction "PB8_95") (pintype "bidirectional"))
      (node (ref "TP104") (pin "TP") (pinfunction "TP_TP") (pintype "input"))
    )
    (net (code "51") (name "RTC_RST") (class "Default")
      (node (ref "IC103") (pin "96") (pinfunction "PB9_96") (pintype "bidirectional"))
      (node (ref "TP105") (pin "TP") (pinfunction "TP_TP") (pintype "input"))
    )
    (net (code "52") (name "RTC_SCL") (class "Default")
      (node (ref "IC103") (pin "92") (pinfunction "PB6_92") (pintype "bidirectional"))
      (node (ref "TP102") (pin "TP") (pinfunction "TP_TP") (pintype "input"))
    )
    (net (code "53") (name "RTC_SDA") (class "Default")
      (node (ref "IC103") (pin "93") (pinfunction "PB7_93") (pintype "bidirectional"))
      (node (ref "TP103") (pin "TP") (pinfunction "TP_TP") (pintype "input"))
    )
    (net (code "54") (name "SWCLK") (class "Default")
      (node (ref "DEBUG") (pin "2") (pinfunction "2_2") (pintype "passive"))
      (node (ref "IC103") (pin "76") (pinfunction "PA14_76") (pintype "bidirectional"))
    )
    (net (code "55") (name "SWD") (class "Default")
      (node (ref "DEBUG") (pin "4") (pinfunction "4_4") (pintype "passive"))
      (node (ref "IC103") (pin "72") (pinfunction "PA13_72") (pintype "bidirectional"))
    )
    (net (code "56") (name "SWO") (class "Default")
      (node (ref "DEBUG") (pin "5") (pinfunction "5_5") (pintype "passive"))
      (node (ref "SJ100") (pin "2") (pinfunction "2_2") (pintype "passive"))
      (node (ref "SJ101") (pin "2") (pinfunction "2_2") (pintype "passive"))
    )
    (net (code "57") (name "TACH_MCU") (class "Default")
      (node (ref "CON101") (pin "1") (pinfunction "1_1") (pintype "passive"))
      (node (ref "IC100") (pin "4") (pinfunction "OUT_4") (pintype "output"))
      (node (ref "IC103") (pin "71") (pinfunction "PA12_71") (pintype "bidirectional"))
      (node (ref "TP100") (pin "TP") (pinfunction "TP_TP") (pintype "input"))
    )
    (net (code "58") (name "unconnected-(IC103A-PA0-Pad23)") (class "Default")
      (node (ref "IC103") (pin "23") (pinfunction "PA0_23") (pintype "bidirectional"))
    )
    (net (code "59") (name "unconnected-(IC103A-PA1-Pad24)") (class "Default")
      (node (ref "IC103") (pin "24") (pinfunction "PA1_24") (pintype "bidirectional"))
    )
    (net (code "60") (name "unconnected-(IC103A-PA2-Pad25)") (class "Default")
      (node (ref "IC103") (pin "25") (pinfunction "PA2_25") (pintype "bidirectional"))
    )
    (net (code "61") (name "unconnected-(IC103A-PA3-Pad26)") (class "Default")
      (node (ref "IC103") (pin "26") (pinfunction "PA3_26") (pintype "bidirectional"))
    )
    (net (code "62") (name "unconnected-(IC103A-PA4-Pad29)") (class "Default")
      (node (ref "IC103") (pin "29") (pinfunction "PA4_29") (pintype "bidirectional"))
    )
    (net (code "63") (name "unconnected-(IC103A-PA5-Pad30)") (class "Default")
      (node (ref "IC103") (pin "30") (pinfunction "PA5_30") (pintype "bidirectional"))
    )
    (net (code "64") (name "unconnected-(IC103A-PA6-Pad31)") (class "Default")
      (node (ref "IC103") (pin "31") (pinfunction "PA6_31") (pintype "bidirectional"))
    )
    (net (code "65") (name "unconnected-(IC103A-PA7-Pad32)") (class "Default")
      (node (ref "IC103") (pin "32") (pinfunction "PA7_32") (pintype "bidirectional"))
    )
    (net (code "66") (name "unconnected-(IC103A-PA8-Pad67)") (class "Default")
      (node (ref "IC103") (pin "67") (pinfunction "PA8_67") (pintype "bidirectional"))
    )
    (net (code "67") (name "unconnected-(IC103A-PA10-Pad69)") (class "Default")
      (node (ref "IC103") (pin "69") (pinfunction "PA10_69") (pintype "bidirectional"))
    )
    (net (code "68") (name "unconnected-(IC103A-PA11-Pad70)") (class "Default")
      (node (ref "IC103") (pin "70") (pinfunction "PA11_70") (pintype "bidirectional"))
    )
    (net (code "69") (name "unconnected-(IC103A-PB1-Pad36)") (class "Default")
      (node (ref "IC103") (pin "36") (pinfunction "PB1_36") (pintype "bidirectional"))
    )
    (net (code "70") (name "unconnected-(IC103A-PB2-Pad37)") (class "Default")
      (node (ref "IC103") (pin "37") (pinfunction "PB2_37") (pintype "bidirectional"))
    )
    (net (code "71") (name "unconnected-(IC103A-PB4-Pad90)") (class "Default")
      (node (ref "IC103") (pin "90") (pinfunction "PB4_90") (pintype "bidirectional"))
    )
    (net (code "72") (name "unconnected-(IC103A-PB5-Pad91)") (class "Default")
      (node (ref "IC103") (pin "91") (pinfunction "PB5_91") (pintype "bidirectional"))
    )
    (net (code "73") (name "unconnected-(IC103A-PB10-Pad47)") (class "Default")
      (node (ref "IC103") (pin "47") (pinfunction "PB10_47") (pintype "bidirectional"))
    )
    (net (code "74") (name "unconnected-(IC103A-PB11-Pad48)") (class "Default")
      (node (ref "IC103") (pin "48") (pinfunction "PB11_48") (pintype "bidirectional"))
    )
    (net (code "75") (name "unconnected-(IC103A-PB12-Pad51)") (class "Default")
      (node (ref "IC103") (pin "51") (pinfunction "PB12_51") (pintype "bidirectional"))
    )
    (net (code "76") (name "unconnected-(IC103A-PB14-Pad53)") (class "Default")
      (node (ref "IC103") (pin "53") (pinfunction "PB14_53") (pintype "bidirectional"))
    )
    (net (code "77") (name "unconnected-(IC103A-PB15-Pad54)") (class "Default")
      (node (ref "IC103") (pin "54") (pinfunction "PB15_54") (pintype "bidirectional"))
    )
    (net (code "78") (name "unconnected-(IC103A-PC2-Pad17)") (class "Default")
      (node (ref "IC103") (pin "17") (pinfunction "PC2_17") (pintype "bidirectional"))
    )
    (net (code "79") (name "unconnected-(IC103A-PC4-Pad33)") (class "Default")
      (node (ref "IC103") (pin "33") (pinfunction "PC4_33") (pintype "bidirectional"))
    )
    (net (code "80") (name "unconnected-(IC103A-PC6-Pad63)") (class "Default")
      (node (ref "IC103") (pin "63") (pinfunction "PC6_63") (pintype "bidirectional"))
    )
    (net (code "81") (name "unconnected-(IC103A-PC7-Pad64)") (class "Default")
      (node (ref "IC103") (pin "64") (pinfunction "PC7_64") (pintype "bidirectional"))
    )
    (net (code "82") (name "unconnected-(IC103A-PC8-Pad65)") (class "Default")
      (node (ref "IC103") (pin "65") (pinfunction "PC8_65") (pintype "bidirectional"))
    )
    (net (code "83") (name "unconnected-(IC103A-PC10-Pad78)") (class "Default")
      (node (ref "IC103") (pin "78") (pinfunction "PC10_78") (pintype "bidirectional"))
    )
    (net (code "84") (name "unconnected-(IC103A-PC11-Pad79)") (class "Default")
      (node (ref "IC103") (pin "79") (pinfunction "PC11_79") (pintype "bidirectional"))
    )
    (net (code "85") (name "unconnected-(IC103A-PC12-Pad80)") (class "Default")
      (node (ref "IC103") (pin "80") (pinfunction "PC12_80") (pintype "bidirectional"))
    )
    (net (code "86") (name "unconnected-(IC103A-PC14-Pad8)") (class "Default")
      (node (ref "IC103") (pin "8") (pinfunction "PC14_8") (pintype "bidirectional"))
    )
    (net (code "87") (name "unconnected-(IC103A-PC15-Pad9)") (class "Default")
      (node (ref "IC103") (pin "9") (pinfunction "PC15_9") (pintype "bidirectional"))
    )
    (net (code "88") (name "unconnected-(IC103A-PD7-Pad88)") (class "Default")
      (node (ref "IC103") (pin "88") (pinfunction "PD7_88") (pintype "bidirectional"))
    )
    (net (code "89") (name "unconnected-(IC103A-PD8-Pad55)") (class "Default")
      (node (ref "IC103") (pin "55") (pinfunction "PD8_55") (pintype "bidirectional"))
    )
    (net (code "90") (name "unconnected-(IC103A-PD9-Pad56)") (class "Default")
      (node (ref "IC103") (pin "56") (pinfunction "PD9_56") (pintype "bidirectional"))
    )
    (net (code "91") (name "unconnected-(IC103A-PD12-Pad59)") (class "Default")
      (node (ref "IC103") (pin "59") (pinfunction "PD12_59") (pintype "bidirectional"))
    )
    (net (code "92") (name "unconnected-(IC103A-PD13-Pad60)") (class "Default")
      (node (ref "IC103") (pin "60") (pinfunction "PD13_60") (pintype "bidirectional"))
    )
    (net (code "93") (name "unconnected-(IC103A-PE0-Pad97)") (class "Default")
      (node (ref "IC103") (pin "97") (pinfunction "PE0_97") (pintype "bidirectional"))
    )
    (net (code "94") (name "unconnected-(IC103A-PE1-Pad98)") (class "Default")
      (node (ref "IC103") (pin "98") (pinfunction "PE1_98") (pintype "bidirectional"))
    )
    (net (code "95") (name "unconnected-(IC103A-PE2-Pad1)") (class "Default")
      (node (ref "IC103") (pin "1") (pinfunction "PE2_1") (pintype "bidirectional"))
    )
    (net (code "96") (name "unconnected-(IC103A-PE3-Pad2)") (class "Default")
      (node (ref "IC103") (pin "2") (pinfunction "PE3_2") (pintype "bidirectional"))
    )
    (net (code "97") (name "unconnected-(IC103A-PE4-Pad3)") (class "Default")
      (node (ref "IC103") (pin "3") (pinfunction "PE4_3") (pintype "bidirectional"))
    )
    (net (code "98") (name "unconnected-(IC103A-PE6-Pad5)") (class "Default")
      (node (ref "IC103") (pin "5") (pinfunction "PE6_5") (pintype "bidirectional"))
    )
    (net (code "99") (name "unconnected-(IC103A-PE7-Pad38)") (class "Default")
      (node (ref "IC103") (pin "38") (pinfunction "PE7_38") (pintype "bidirectional"))
    )
    (net (code "100") (name "unconnected-(IC103A-PE8-Pad39)") (class "Default")
      (node (ref "IC103") (pin "39") (pinfunction "PE8_39") (pintype "bidirectional"))
    )
    (net (code "101") (name "unconnected-(IC103A-PE9-Pad40)") (class "Default")
      (node (ref "IC103") (pin "40") (pinfunction "PE9_40") (pintype "bidirectional"))
    )
    (net (code "102") (name "unconnected-(IC103A-PE10-Pad41)") (class "Default")
      (node (ref "IC103") (pin "41") (pinfunction "PE10_41") (pintype "bidirectional"))
    )
    (net (code "103") (name "unconnected-(IC103A-PE12-Pad43)") (class "Default")
      (node (ref "IC103") (pin "43") (pinfunction "PE12_43") (pintype "bidirectional"))
    )
    (net (code "104") (name "unconnected-(IC103A-PE13-Pad44)") (class "Default")
      (node (ref "IC103") (pin "44") (pinfunction "PE13_44") (pintype "bidirectional"))
    )
    (net (code "105") (name "unconnected-(IC103A-PE14-Pad45)") (class "Default")
      (node (ref "IC103") (pin "45") (pinfunction "PE14_45") (pintype "bidirectional"))
    )
    (net (code "106") (name "unconnected-(IC103A-PE15-Pad46)") (class "Default")
      (node (ref "IC103") (pin "46") (pinfunction "PE15_46") (pintype "bidirectional"))
    )
    (net (code "107") (name "unconnected-(U$100-NC-Pad12)") (class "Default")
      (node (ref "U$100") (pin "12") (pinfunction "NC_12") (pintype "bidirectional"))
    )
  )
)
